# Button_Block.net
KiCad netlist of a schematic drawn in Altium Designer
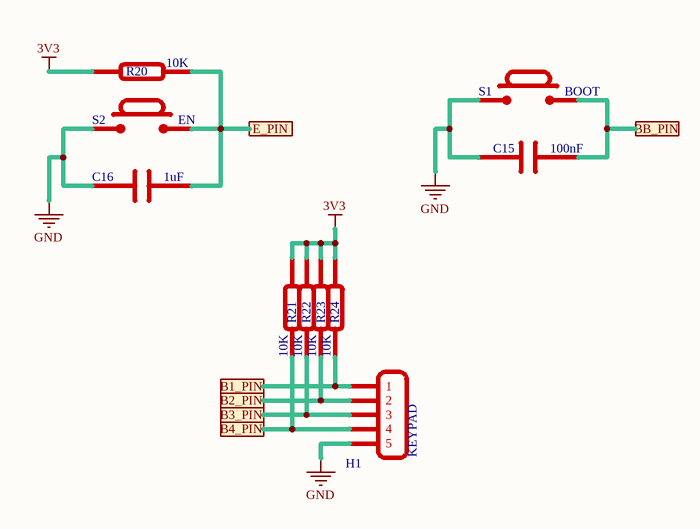
[diagram p0: Button_Block.SchDoc]

(export (version "E")
  (design (tool "Eeschema 10.0.6"))
  (components
    (comp (ref "C15")
      (value "100nF")
      (footprint "C0603")
      (description "Ceramic Capacitor")
      (libsource (lib "CTAI-Library") (part "CAP-CER"))
    )
    (comp (ref "C16")
      (value "1uF")
      (footprint "C0603")
      (description "Ceramic Capacitor")
      (libsource (lib "CTAI-Library") (part "CAP-CER"))
    )
    (comp (ref "H1")
      (value "KEYPAD")
      (footprint "XH-2.54-5P")
      (description "Connector 5 Pole")
      (libsource (lib "CTAI-Library") (part "CONN-5P"))
    )
    (comp (ref "R20")
      (value "10K")
      (footprint "R0603")
      (description "Resistor")
      (libsource (lib "CTAI-Library") (part "Resistor"))
    )
    (comp (ref "R21")
      (value "10K")
      (footprint "R0603")
      (description "Resistor")
      (libsource (lib "CTAI-Library") (part "Resistor"))
    )
    (comp (ref "R22")
      (value "10K")
      (footprint "R0603")
      (description "Resistor")
      (libsource (lib "CTAI-Library") (part "Resistor"))
    )
    (comp (ref "R23")
      (value "10K")
      (footprint "R0603")
      (description "Resistor")
      (libsource (lib "CTAI-Library") (part "Resistor"))
    )
    (comp (ref "R24")
      (value "10K")
      (footprint "R0603")
      (description "Resistor")
      (libsource (lib "CTAI-Library") (part "Resistor"))
    )
    (comp (ref "S1")
      (value "BOOT")
      (footprint "BTN-SMD-3x6")
      (description "Tactile Switch 2 pole")
      (libsource (lib "CTAI-Library") (part "Button-2P"))
    )
    (comp (ref "S2")
      (value "EN")
      (footprint "BTN-SMD-3x6")
      (description "Tactile Switch 2 pole")
      (libsource (lib "CTAI-Library") (part "Button-2P"))
    )
  )
  (nets
    (net (code "1") (name "/B1_PIN") (class "Default")
      (node (ref "H1") (pin "1") (pinfunction "1_1") (pintype "passive"))
      (node (ref "R24") (pin "2") (pinfunction "2_2") (pintype "passive"))
    )
    (net (code "2") (name "/B2_PIN") (class "Default")
      (node (ref "H1") (pin "2") (pinfunction "2_2") (pintype "passive"))
      (node (ref "R23") (pin "2") (pinfunction "2_2") (pintype "passive"))
    )
    (net (code "3") (name "/B3_PIN") (class "Default")
      (node (ref "H1") (pin "3") (pinfunction "3_3") (pintype "passive"))
      (node (ref "R22") (pin "2") (pinfunction "2_2") (pintype "passive"))
    )
    (net (code "4") (name "/B4_PIN") (class "Default")
      (node (ref "H1") (pin "4") (pinfunction "4_4") (pintype "passive"))
      (node (ref "R21") (pin "2") (pinfunction "2_2") (pintype "passive"))
    )
    (net (code "5") (name "/BB_PIN") (class "Default")
      (node (ref "C15") (pin "1") (pintype "passive"))
      (node (ref "S1") (pin "2") (pintype "passive"))
    )
    (net (code "6") (name "/E_PIN") (class "Default")
      (node (ref "C16") (pin "1") (pintype "passive"))
      (node (ref "R20") (pin "1") (pinfunction "1_1") (pintype "passive"))
      (node (ref "S2") (pin "2") (pintype "passive"))
    )
    (net (code "7") (name "3V3") (class "Default")
      (node (ref "R20") (pin "2") (pinfunction "2_2") (pintype "passive"))
      (node (ref "R21") (pin "1") (pinfunction "1_1") (pintype "passive"))
      (node (ref "R22") (pin "1") (pinfunction "1_1") (pintype "passive"))
      (node (ref "R23") (pin "1") (pinfunction "1_1") (pintype "passive"))
      (node (ref "R24") (pin "1") (pinfunction "1_1") (pintype "passive"))
    )
    (net (code "8") (name "GND") (class "Default")
      (node (ref "C15") (pin "2") (pintype "passive"))
      (node (ref "C16") (pin "2") (pintype "passive"))
      (node (ref "H1") (pin "5") (pinfunction "5_5") (pintype "passive"))
      (node (ref "S1") (pin "1") (pintype "passive"))
      (node (ref "S2") (pin "1") (pintype "passive"))
    )
  )
)
